# PROC091F_RST_GPIOs_I2C.net
KiCad netlist of a schematic drawn in Altium Designer
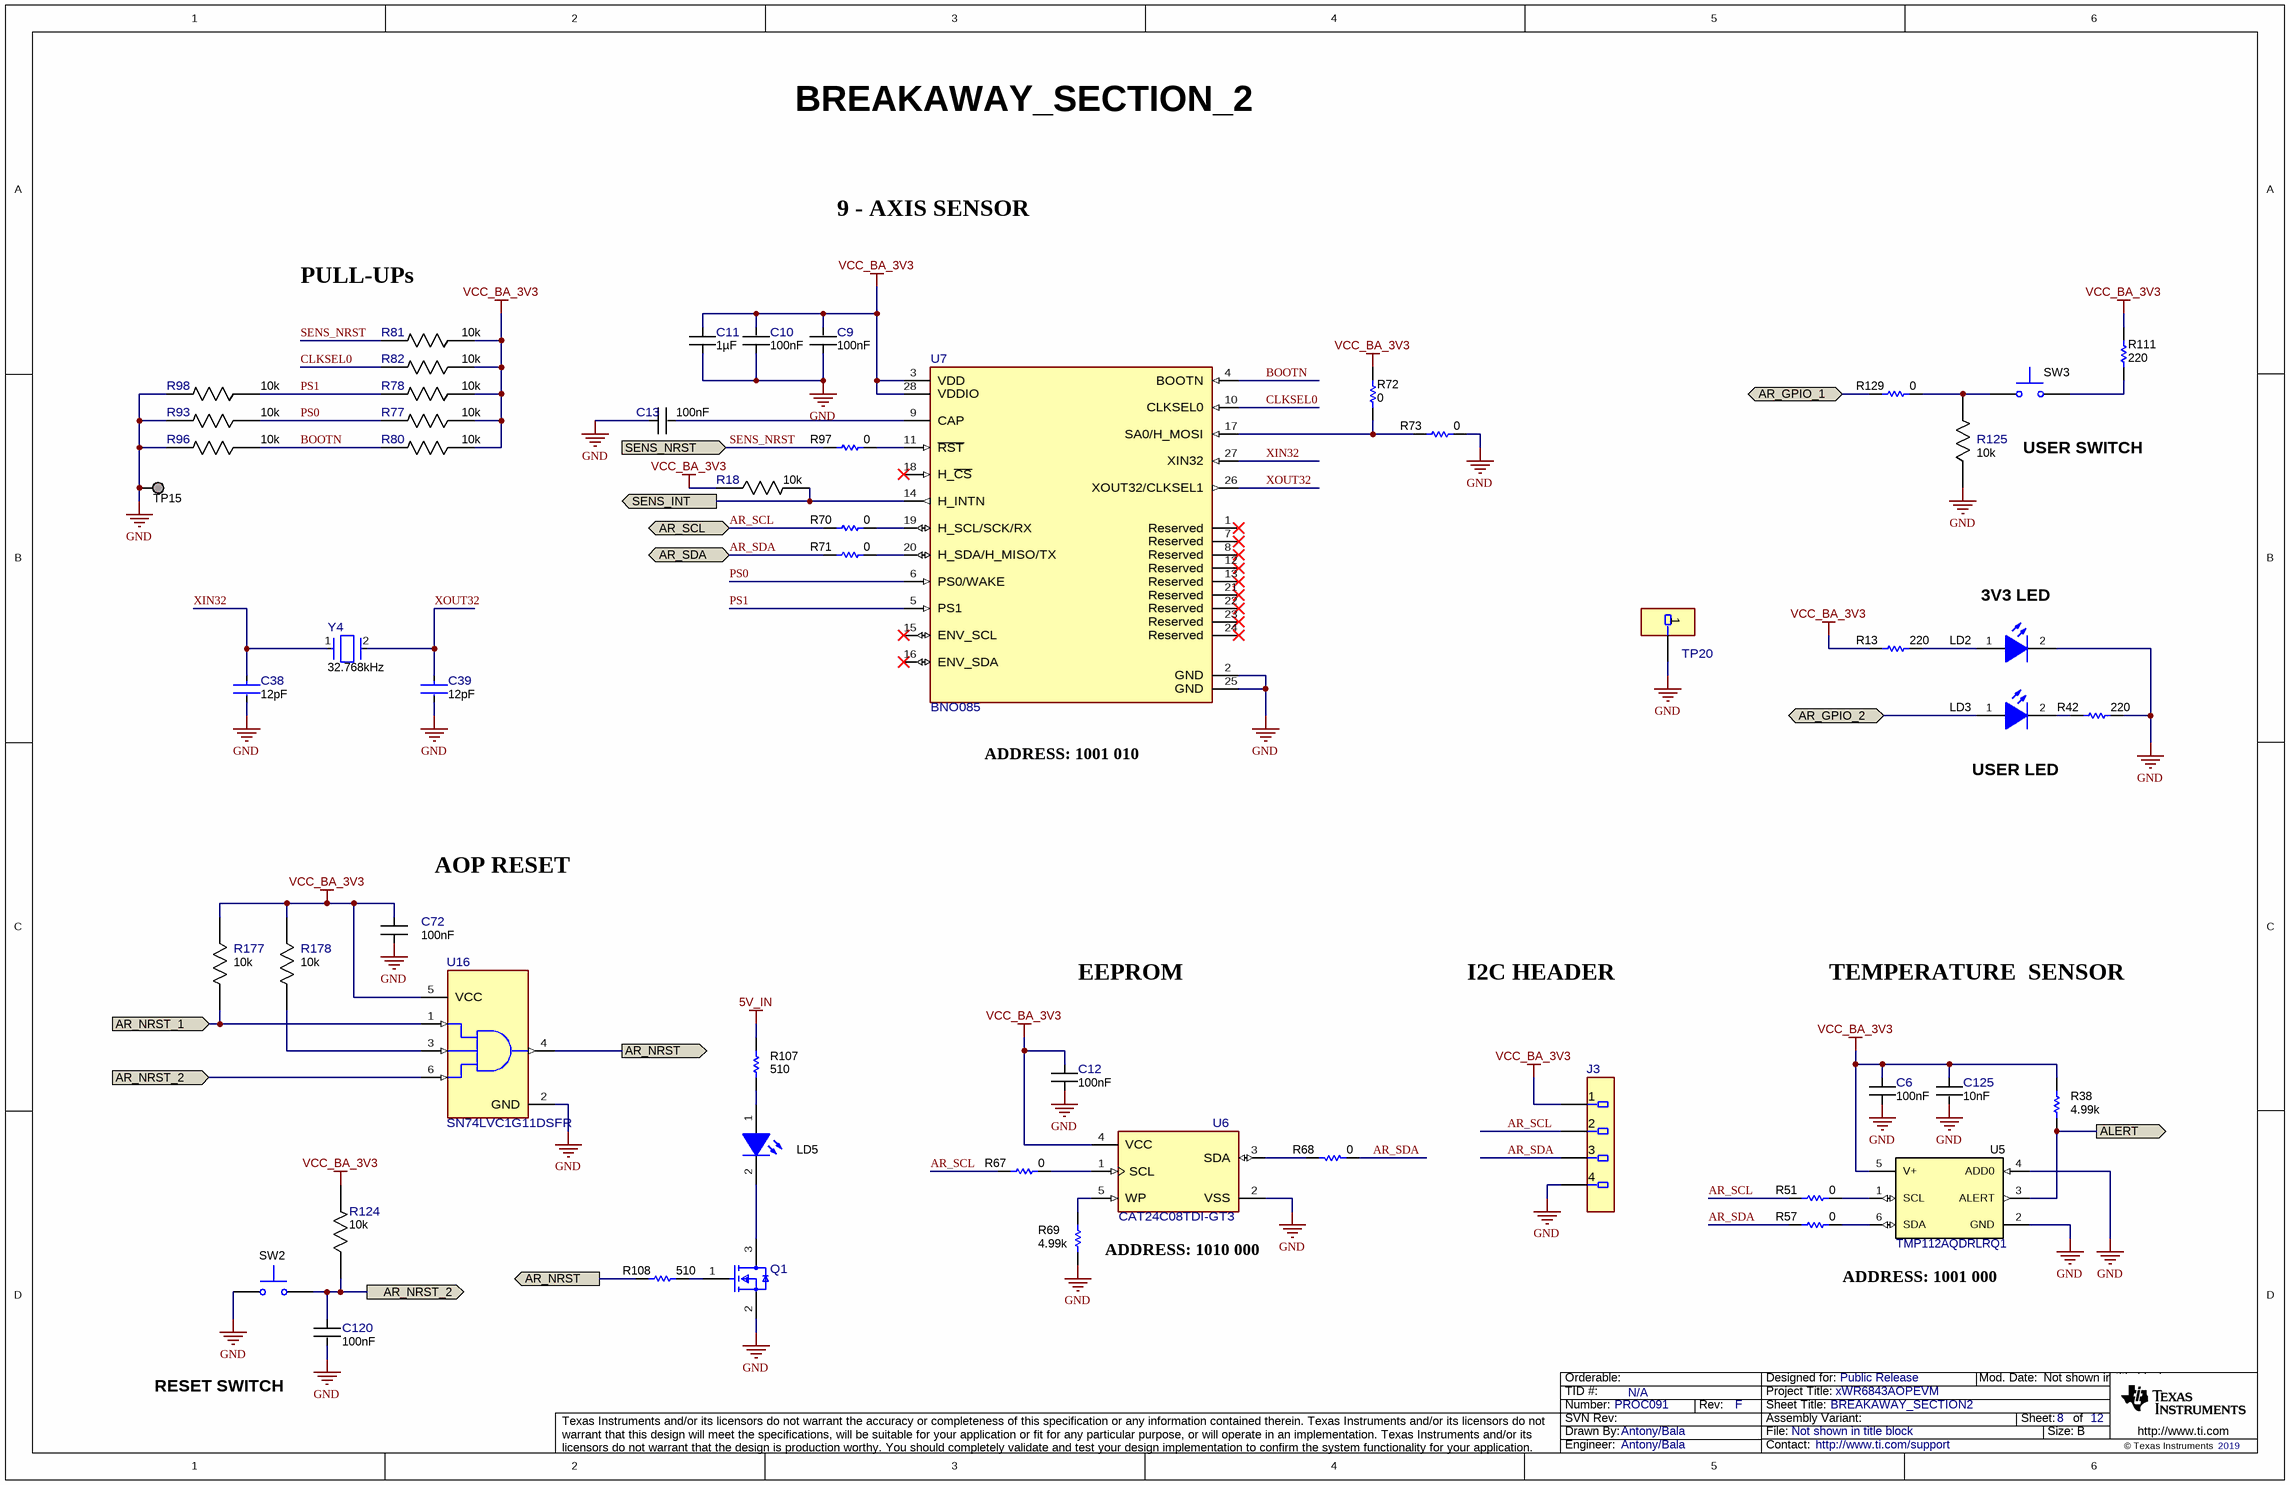
[diagram p0: PROC091F_RST_GPIOs_I2C.SchDoc]

(export (version "E")
  (design (tool "Eeschema 10.0.6"))
  (components
    (comp (ref "C6")
      (value "GRM033R6YA104KE14D")
      (footprint "FP-GRM033R6YA104KE14D_0201 (0603 Metric)-IPC_C")
      (description "Cap Ceramic 0.1uF 35V X5R 10% Pad SMD 0201 85C T/R")
      (fields (field (name "CAP_F") "100nF") (field (name "MANUFACTURER") "Murata Electronics North America"))
      (libsource (lib "Altium Vault - TI") (part "SYM-B32642B0223J"))
    )
    (comp (ref "C9")
      (value "GRM033R6YA104KE14D")
      (footprint "FP-GRM033R6YA104KE14D_0201 (0603 Metric)-IPC_C")
      (description "Cap Ceramic 0.1uF 35V X5R 10% Pad SMD 0201 85C T/R")
      (fields (field (name "CAP_F") "100nF") (field (name "MANUFACTURER") "Murata Electronics North America"))
      (libsource (lib "Altium Vault - TI") (part "SYM-B32642B0223J"))
    )
    (comp (ref "C10")
      (value "GRM033R6YA104KE14D")
      (footprint "FP-GRM033R6YA104KE14D_0201 (0603 Metric)-IPC_C")
      (description "Cap Ceramic 0.1uF 35V X5R 10% Pad SMD 0201 85C T/R")
      (fields (field (name "CAP_F") "100nF") (field (name "MANUFACTURER") "Murata Electronics North America"))
      (libsource (lib "Altium Vault - TI") (part "SYM-B32642B0223J"))
    )
    (comp (ref "C11")
      (value "CL03A105MO3NRNH")
      (footprint "FP-CL03A105MO3NRNH_0201-IPC_C")
      (description "1µF ±20% 16V Ceramic Capacitor X5R 0201")
      (fields (field (name "CAP_F") "1µF") (field (name "MANUFACTURER") "Samsung Electro-Mechanics"))
      (libsource (lib "Altium Vault - TI") (part "SYM-B32642B0223J"))
    )
    (comp (ref "C12")
      (value "GRM033R6YA104KE14D")
      (footprint "FP-GRM033R6YA104KE14D_0201 (0603 Metric)-IPC_C")
      (description "Cap Ceramic 0.1uF 35V X5R 10% Pad SMD 0201 85C T/R")
      (fields (field (name "CAP_F") "100nF") (field (name "MANUFACTURER") "Murata Electronics North America"))
      (libsource (lib "Altium Vault - TI") (part "SYM-B32642B0223J"))
    )
    (comp (ref "C13")
      (value "GRM033R6YA104KE14D")
      (footprint "FP-GRM033R6YA104KE14D_0201 (0603 Metric)-IPC_C")
      (description "Cap Ceramic 0.1uF 35V X5R 10% Pad SMD 0201 85C T/R")
      (fields (field (name "CAP_F") "100nF") (field (name "MANUFACTURER") "Murata Electronics North America"))
      (libsource (lib "Altium Vault - TI") (part "SYM-B32642B0223J"))
    )
    (comp (ref "C38")
      (value "250R05L120JV4T")
      (footprint "FP-250R05L120JV4T_0201-IPC_C")
      (description "CAP CER 12PF 25V C0G/NP0 0201")
      (fields (field (name "CAP_F") "12pF") (field (name "MANUFACTURER") "Johanson Technology Inc."))
      (libsource (lib "Altium Vault - TI") (part "SYM-CL31B335KAHVPNE"))
    )
    (comp (ref "C39")
      (value "250R05L120JV4T")
      (footprint "FP-250R05L120JV4T_0201-IPC_C")
      (description "CAP CER 12PF 25V C0G/NP0 0201")
      (fields (field (name "CAP_F") "12pF") (field (name "MANUFACTURER") "Johanson Technology Inc."))
      (libsource (lib "Altium Vault - TI") (part "SYM-CL31B335KAHVPNE"))
    )
    (comp (ref "C72")
      (value "GRM033R6YA104KE14D")
      (footprint "FP-GRM033R6YA104KE14D_0201 (0603 Metric)-IPC_C")
      (description "Cap Ceramic 0.1uF 35V X5R 10% Pad SMD 0201 85C T/R")
      (fields (field (name "CAP_F") "100nF") (field (name "MANUFACTURER") "Murata Electronics North America"))
      (libsource (lib "Altium Vault - TI") (part "SYM-B32642B0223J"))
    )
    (comp (ref "C120")
      (value "GRM033R6YA104KE14D")
      (footprint "FP-GRM033R6YA104KE14D_0201 (0603 Metric)-IPC_C")
      (description "Cap Ceramic 0.1uF 35V X5R 10% Pad SMD 0201 85C T/R")
      (fields (field (name "CAP_F") "100nF") (field (name "MANUFACTURER") "Murata Electronics North America"))
      (libsource (lib "Altium Vault - TI") (part "SYM-B32642B0223J"))
    )
    (comp (ref "C125")
      (value "CL03A103KA3NNNC")
      (footprint "FP-CL03A103KA3NNNC_0201-IPC_C")
      (description "CAP CER 10000PF 25V X5R 0201")
      (fields
        (field (name "CAP_F") "10nF")
        (field (name "MANUFACTURER") "Samsung Electro-Mechanics America, Inc")
      )
      (libsource (lib "Altium Vault - TI") (part "SYM-B32642B0223J"))
    )
    (comp (ref "J3")
      (value "M50-3930442")
      (footprint "FP-M50-3930442_HDR4-Recommended_Land_Pattern")
      (description "CONN HDR 1.27MM R/A AU 4POS")
      (fields (field (name "MANUFACTURER") "Harwin Inc."))
      (libsource (lib "Altium Vault - TI") (part "SYM-M50-3930442"))
    )
    (comp (ref "LD2")
      (value "APHHS1005CGCK")
      (footprint "APHHS1005_Green")
      (description "LED, Green, SMD")
      (fields (field (name "MANUFACTURER") "Kingbright"))
      (libsource (lib "Altium Vault - TI") (part "LED"))
    )
    (comp (ref "LD3")
      (value "APHHS1005CGCK")
      (footprint "APHHS1005_Green")
      (description "LED, Green, SMD")
      (fields (field (name "MANUFACTURER") "Kingbright"))
      (libsource (lib "Altium Vault - TI") (part "LED"))
    )
    (comp (ref "LD5")
      (value "APHHS1005CGCK")
      (footprint "APHHS1005_Green")
      (description "LED, Green, SMD")
      (fields (field (name "MANUFACTURER") "Kingbright"))
      (libsource (lib "Altium Vault - TI") (part "LED"))
    )
    (comp (ref "Q1")
      (value "BSS123-7-F")
      (footprint "FP-BSS123-7-F_SOT23-IPC_C")
      (description "MOSFET N-CH 100V 170MA SOT23-3")
      (fields (field (name "MANUFACTURER") "Diodes Incorporated"))
      (libsource (lib "Altium Vault - TI") (part "SYM-BSS123-7-F"))
    )
    (comp (ref "R13")
      (value "220")
      (footprint "0201L")
      (description "RES, 220, 5%, 0.05 W, 0201")
      (fields
        (field (name "MANUFACTURER") "Yageo America")
        (field (name "PARTNUMBER") "RC0201JR-07220RL")
        (field (name "PUBLISHER") "Texas Instruments")
      )
      (libsource (lib "Altium Vault - TI") (part "Resistor"))
    )
    (comp (ref "R18")
      (value "RR0306P-103-D")
      (footprint "FP-RR0306P-103-D_0201-IPC_C")
      (description "10 kOhms ±0.5% 0.05W, 1/20W Chip Resistor 0201 (0603 Metric)  Thin Film")
      (fields (field (name "MANUFACTURER") "Susumu") (field (name "RES_OHM") "10k"))
      (libsource (lib "Altium Vault - TI") (part "SYM-PMR18EZPJ000"))
    )
    (comp (ref "R38")
      (value "4.99k")
      (footprint "0201L")
      (description "RES, 4.99 k, 1%, 0.05 W, 0201")
      (fields
        (field (name "MANUFACTURER") "Yageo America")
        (field (name "PARTNUMBER") "RC0201FR-074K99L")
        (field (name "PUBLISHER") "Texas Instruments")
      )
      (libsource (lib "Altium Vault - TI") (part "Resistor"))
    )
    (comp (ref "R42")
      (value "220")
      (footprint "0201L")
      (description "RES, 220, 5%, 0.05 W, 0201")
      (fields
        (field (name "MANUFACTURER") "Yageo America")
        (field (name "PARTNUMBER") "RC0201JR-07220RL")
        (field (name "PUBLISHER") "Texas Instruments")
      )
      (libsource (lib "Altium Vault - TI") (part "Resistor"))
    )
    (comp (ref "R51")
      (value "RC0201JR-070RL")
      (footprint "FP-RC0201JR-070RL_0201 (0603 Metric)-MFG")
      (description "RES SMD 0 OHM JUMPER 1/20W 0201")
      (fields (field (name "MANUFACTURER") "Yageo") (field (name "RES_OHM") "0"))
      (libsource (lib "Altium Vault - TI") (part "SYM-WSR3R1500F"))
    )
    (comp (ref "R57")
      (value "RC0201JR-070RL")
      (footprint "FP-RC0201JR-070RL_0201 (0603 Metric)-MFG")
      (description "RES SMD 0 OHM JUMPER 1/20W 0201")
      (fields (field (name "MANUFACTURER") "Yageo") (field (name "RES_OHM") "0"))
      (libsource (lib "Altium Vault - TI") (part "SYM-WSR3R1500F"))
    )
    (comp (ref "R67")
      (value "RC0201JR-070RL")
      (footprint "FP-RC0201JR-070RL_0201 (0603 Metric)-MFG")
      (description "RES SMD 0 OHM JUMPER 1/20W 0201")
      (fields (field (name "MANUFACTURER") "Yageo") (field (name "RES_OHM") "0"))
      (libsource (lib "Altium Vault - TI") (part "SYM-WSR3R1500F"))
    )
    (comp (ref "R68")
      (value "RC0201JR-070RL")
      (footprint "FP-RC0201JR-070RL_0201 (0603 Metric)-MFG")
      (description "RES SMD 0 OHM JUMPER 1/20W 0201")
      (fields (field (name "MANUFACTURER") "Yageo") (field (name "RES_OHM") "0"))
      (libsource (lib "Altium Vault - TI") (part "SYM-WSR3R1500F"))
    )
    (comp (ref "R69")
      (value "4.99k")
      (footprint "0201L")
      (description "RES, 4.99 k, 1%, 0.05 W, 0201")
      (fields
        (field (name "MANUFACTURER") "Yageo America")
        (field (name "PARTNUMBER") "RC0201FR-074K99L")
        (field (name "PUBLISHER") "Texas Instruments")
      )
      (libsource (lib "Altium Vault - TI") (part "Resistor"))
    )
    (comp (ref "R70")
      (value "RC0201JR-070RL")
      (footprint "FP-RC0201JR-070RL_0201 (0603 Metric)-MFG")
      (description "RES SMD 0 OHM JUMPER 1/20W 0201")
      (fields (field (name "MANUFACTURER") "Yageo") (field (name "RES_OHM") "0"))
      (libsource (lib "Altium Vault - TI") (part "SYM-WSR3R1500F"))
    )
    (comp (ref "R71")
      (value "RC0201JR-070RL")
      (footprint "FP-RC0201JR-070RL_0201 (0603 Metric)-MFG")
      (description "RES SMD 0 OHM JUMPER 1/20W 0201")
      (fields (field (name "MANUFACTURER") "Yageo") (field (name "RES_OHM") "0"))
      (libsource (lib "Altium Vault - TI") (part "SYM-WSR3R1500F"))
    )
    (comp (ref "R72")
      (value "RC0201JR-070RL")
      (footprint "FP-RC0201JR-070RL_0201 (0603 Metric)-IPC_C")
      (description "RES SMD 0 OHM JUMPER 1/20W 0201")
      (fields (field (name "MANUFACTURER") "Yageo") (field (name "RES_OHM") "0"))
      (libsource (lib "Altium Vault - TI") (part "SYM-WSR3R1500F"))
    )
    (comp (ref "R73")
      (value "RC0201JR-070RL")
      (footprint "FP-RC0201JR-070RL_0201 (0603 Metric)-IPC_C")
      (description "RES SMD 0 OHM JUMPER 1/20W 0201")
      (fields (field (name "MANUFACTURER") "Yageo") (field (name "RES_OHM") "0"))
      (libsource (lib "Altium Vault - TI") (part "SYM-WSR3R1500F"))
    )
    (comp (ref "R77")
      (value "RR0306P-103-D")
      (footprint "FP-RR0306P-103-D_0201-IPC_C")
      (description "10 kOhms ±0.5% 0.05W, 1/20W Chip Resistor 0201 (0603 Metric)  Thin Film")
      (fields (field (name "MANUFACTURER") "Susumu") (field (name "RES_OHM") "10k"))
      (libsource (lib "Altium Vault - TI") (part "SYM-PMR18EZPJ000"))
    )
    (comp (ref "R78")
      (value "RR0306P-103-D")
      (footprint "FP-RR0306P-103-D_0201-IPC_C")
      (description "10 kOhms ±0.5% 0.05W, 1/20W Chip Resistor 0201 (0603 Metric)  Thin Film")
      (fields (field (name "MANUFACTURER") "Susumu") (field (name "RES_OHM") "10k"))
      (libsource (lib "Altium Vault - TI") (part "SYM-PMR18EZPJ000"))
    )
    (comp (ref "R80")
      (value "RR0306P-103-D")
      (footprint "FP-RR0306P-103-D_0201-IPC_C")
      (description "10 kOhms ±0.5% 0.05W, 1/20W Chip Resistor 0201 (0603 Metric)  Thin Film")
      (fields (field (name "MANUFACTURER") "Susumu") (field (name "RES_OHM") "10k"))
      (libsource (lib "Altium Vault - TI") (part "SYM-PMR18EZPJ000"))
    )
    (comp (ref "R81")
      (value "RR0306P-103-D")
      (footprint "FP-RR0306P-103-D_0201-IPC_C")
      (description "10 kOhms ±0.5% 0.05W, 1/20W Chip Resistor 0201 (0603 Metric)  Thin Film")
      (fields (field (name "MANUFACTURER") "Susumu") (field (name "RES_OHM") "10k"))
      (libsource (lib "Altium Vault - TI") (part "SYM-PMR18EZPJ000"))
    )
    (comp (ref "R82")
      (value "RR0306P-103-D")
      (footprint "FP-RR0306P-103-D_0201-IPC_C")
      (description "10 kOhms ±0.5% 0.05W, 1/20W Chip Resistor 0201 (0603 Metric)  Thin Film")
      (fields (field (name "MANUFACTURER") "Susumu") (field (name "RES_OHM") "10k"))
      (libsource (lib "Altium Vault - TI") (part "SYM-PMR18EZPJ000"))
    )
    (comp (ref "R93")
      (value "RR0306P-103-D")
      (footprint "FP-RR0306P-103-D_0201-IPC_C")
      (description "10 kOhms ±0.5% 0.05W, 1/20W Chip Resistor 0201 (0603 Metric)  Thin Film")
      (fields (field (name "MANUFACTURER") "Susumu") (field (name "RES_OHM") "10k"))
      (libsource (lib "Altium Vault - TI") (part "SYM-PMR18EZPJ000"))
    )
    (comp (ref "R96")
      (value "RR0306P-103-D")
      (footprint "FP-RR0306P-103-D_0201-IPC_C")
      (description "10 kOhms ±0.5% 0.05W, 1/20W Chip Resistor 0201 (0603 Metric)  Thin Film")
      (fields (field (name "MANUFACTURER") "Susumu") (field (name "RES_OHM") "10k"))
      (libsource (lib "Altium Vault - TI") (part "SYM-PMR18EZPJ000"))
    )
    (comp (ref "R97")
      (value "RC0201JR-070RL")
      (footprint "FP-RC0201JR-070RL_0201 (0603 Metric)-IPC_C")
      (description "RES SMD 0 OHM JUMPER 1/20W 0201")
      (fields (field (name "MANUFACTURER") "Yageo") (field (name "RES_OHM") "0"))
      (libsource (lib "Altium Vault - TI") (part "SYM-WSR3R1500F"))
    )
    (comp (ref "R98")
      (value "RR0306P-103-D")
      (footprint "FP-RR0306P-103-D_0201-IPC_C")
      (description "10 kOhms ±0.5% 0.05W, 1/20W Chip Resistor 0201 (0603 Metric)  Thin Film")
      (fields (field (name "MANUFACTURER") "Susumu") (field (name "RES_OHM") "10k"))
      (libsource (lib "Altium Vault - TI") (part "SYM-PMR18EZPJ000"))
    )
    (comp (ref "R107")
      (value "510")
      (footprint "0201L")
      (description "RES, 510, 5%, 0.05 W, 0201")
      (fields
        (field (name "MANUFACTURER") "Yageo America")
        (field (name "PARTNUMBER") "RC0201JR-07510RL")
        (field (name "PUBLISHER") "Texas Instruments")
      )
      (libsource (lib "Altium Vault - TI") (part "Resistor"))
    )
    (comp (ref "R108")
      (value "510")
      (footprint "0201L")
      (description "RES, 510, 5%, 0.05 W, 0201")
      (fields
        (field (name "MANUFACTURER") "Yageo America")
        (field (name "PARTNUMBER") "RC0201JR-07510RL")
        (field (name "PUBLISHER") "Texas Instruments")
      )
      (libsource (lib "Altium Vault - TI") (part "Resistor"))
    )
    (comp (ref "R111")
      (value "220")
      (footprint "0201L")
      (description "RES, 220, 5%, 0.05 W, 0201")
      (fields
        (field (name "MANUFACTURER") "Yageo America")
        (field (name "PARTNUMBER") "RC0201JR-07220RL")
        (field (name "PUBLISHER") "Texas Instruments")
      )
      (libsource (lib "Altium Vault - TI") (part "Resistor"))
    )
    (comp (ref "R124")
      (value "RR0306P-103-D")
      (footprint "FP-RR0306P-103-D_0201-IPC_C")
      (description "10 kOhms ±0.5% 0.05W, 1/20W Chip Resistor 0201 (0603 Metric)  Thin Film")
      (fields (field (name "MANUFACTURER") "Susumu") (field (name "RES_OHM") "10k"))
      (libsource (lib "Altium Vault - TI") (part "SYM-PMR18EZPJ000"))
    )
    (comp (ref "R125")
      (value "RR0306P-103-D")
      (footprint "FP-RR0306P-103-D_0201-IPC_C")
      (description "10 kOhms ±0.5% 0.05W, 1/20W Chip Resistor 0201 (0603 Metric)  Thin Film")
      (fields (field (name "MANUFACTURER") "Susumu") (field (name "RES_OHM") "10k"))
      (libsource (lib "Altium Vault - TI") (part "SYM-PMR18EZPJ000"))
    )
    (comp (ref "R129")
      (value "RC0201JR-070RL")
      (footprint "FP-RC0201JR-070RL_0201 (0603 Metric)-IPC_C")
      (description "RES SMD 0 OHM JUMPER 1/20W 0201")
      (fields (field (name "MANUFACTURER") "Yageo") (field (name "RES_OHM") "0"))
      (libsource (lib "Altium Vault - TI") (part "SYM-WSR3R1500F"))
    )
    (comp (ref "R177")
      (value "RR0306P-103-D")
      (footprint "FP-RR0306P-103-D_0201-IPC_C")
      (description "10 kOhms ±0.5% 0.05W, 1/20W Chip Resistor 0201 (0603 Metric)  Thin Film")
      (fields (field (name "MANUFACTURER") "Susumu") (field (name "RES_OHM") "10k"))
      (libsource (lib "Altium Vault - TI") (part "SYM-PMR18EZPJ000"))
    )
    (comp (ref "R178")
      (value "RR0306P-103-D")
      (footprint "FP-RR0306P-103-D_0201-IPC_C")
      (description "10 kOhms ±0.5% 0.05W, 1/20W Chip Resistor 0201 (0603 Metric)  Thin Film")
      (fields (field (name "MANUFACTURER") "Susumu") (field (name "RES_OHM") "10k"))
      (libsource (lib "Altium Vault - TI") (part "SYM-PMR18EZPJ000"))
    )
    (comp (ref "SW2")
      (value "B3U-1000P")
      (footprint "SW_B3U-1000P")
      (description "SWITCH TACTILE SPST-NO 0.05A 12V")
      (fields
        (field (name "MANUFACTURER") "Omron Electronic Components")
        (field (name "PUBLISHER") "Texas Instruments")
      )
      (libsource (lib "Altium Vault - TI") (part "Switch_PushButton"))
    )
    (comp (ref "SW3")
      (value "B3U-1000P")
      (footprint "SW_B3U-1000P")
      (description "SWITCH TACTILE SPST-NO 0.05A 12V")
      (fields
        (field (name "MANUFACTURER") "Omron Electronic Components")
        (field (name "PUBLISHER") "Texas Instruments")
      )
      (libsource (lib "Altium Vault - TI") (part "Switch_PushButton"))
    )
    (comp (ref "TP15")
      (value "TESTPOINT")
      (footprint "TP_25MIL-SMT")
      (description "TEST POINT.  No entry in BOM.")
      (libsource (lib "Altium Vault - TI") (part "TESTPOINT"))
    )
    (comp (ref "TP20")
      (value "4953")
      (footprint "FP-4953_HDR1-MFG")
      (description "PC Test Point, Loop Brass, Tin Plating 0.047\" (1.19mm) Hole Diameter Mounting Type")
      (fields (field (name "MANUFACTURER") "Keystone Electronics"))
      (libsource (lib "Altium Vault - TI") (part "SYM-4953"))
    )
    (comp (ref "U5")
      (value "TMP112AQDRLRQ1")
      (footprint "DRL0006A")
      (fields
        (field (name "MANUFACTURER") "Texas Instruments")
        (field (name "PUBLISHER") "Texas Instruments")
      )
      (libsource (lib "Altium Vault - TI") (part "TMP112"))
    )
    (comp (ref "U6")
      (value "CAT24C08TDI-GT3")
      (footprint "FP-CAT24C08TDI-GT3_TSOT-23-5-IPC_A")
      (description "8KB I2C SER EEPROM TSOT 23")
      (fields (field (name "MANUFACTURER") "ON Semiconductor"))
      (libsource (lib "Altium Vault - TI") (part "SYM-CAT24C08TDI-GT3"))
    )
    (comp (ref "U7")
      (value "BNO085")
      (footprint "FP-BNO085_LGA28-MFG")
      (description "IMU ACCEL/GYRO/MAG I2C 32BIT")
      (fields (field (name "MANUFACTURER") "Hillcrest Laboratories, Inc."))
      (libsource (lib "Altium Vault - TI") (part "SYM-BNO085"))
    )
    (comp (ref "U16")
      (value "SN74LVC1G11DSFR")
      (footprint "DSF0006A-MFG")
      (description "AND Gate IC 1 Channel  6-SON (1x1)")
      (fields
        (field (name "MOUSER PART NUMBER") "595-SN74LVC1G11DSFR")
        (field (name "DIGIKEY PART NUMBER") "296-30121-1-ND")
      )
      (libsource (lib "Altium Vault - TI") (part "SYM-SN74LVC1G11DSFR"))
    )
    (comp (ref "Y4")
      (value "ABS05W-32.768KHZ-D-2-T")
      (footprint "FP-ABS05W-32.768KHZ-D-2-T_XTAL_SMT_1MM6_1MM0-MFG")
      (description "CRYSTAL 32.768KHZ 4PF SMD")
      (fields (field (name "FREQUENCY_FIXED") "32.768kHz") (field (name "MANUFACTURER") "Abracon LLC"))
      (libsource (lib "Altium Vault - TI") (part "SYM-ABS05W-32.768KHZ-D-2-T"))
    )
  )
  (nets
    (net (code "1") (name "/ALERT") (class "Default")
      (node (ref "R38") (pin "1") (pinfunction "1_1") (pintype "passive"))
      (node (ref "U5") (pin "3") (pinfunction "ALERT_3") (pintype "output"))
    )
    (net (code "2") (name "/AR_GPIO_1") (class "Default")
      (node (ref "R129") (pin "2") (pinfunction "2_2") (pintype "passive"))
    )
    (net (code "3") (name "/AR_GPIO_2") (class "Default")
      (node (ref "LD3") (pin "1") (pinfunction "A_1") (pintype "passive"))
    )
    (net (code "4") (name "/AR_NRST") (class "Default")
      (node (ref "R108") (pin "1") (pinfunction "1_1") (pintype "passive"))
      (node (ref "U16") (pin "4") (pinfunction "Y_4") (pintype "output"))
    )
    (net (code "5") (name "/AR_NRST_1") (class "Default")
      (node (ref "R177") (pin "2") (pinfunction "2_2") (pintype "passive"))
      (node (ref "U16") (pin "1") (pinfunction "A_1") (pintype "input"))
    )
    (net (code "6") (name "/AR_NRST_2") (class "Default")
      (node (ref "C120") (pin "1") (pinfunction "1_1") (pintype "passive"))
      (node (ref "R124") (pin "1") (pinfunction "1_1") (pintype "passive"))
      (node (ref "SW2") (pin "1") (pinfunction "1_1") (pintype "passive"))
      (node (ref "U16") (pin "6") (pinfunction "C_6") (pintype "input"))
    )
    (net (code "7") (name "/AR_SCL") (class "Default")
      (node (ref "J3") (pin "2") (pinfunction "2_2") (pintype "passive"))
      (node (ref "R51") (pin "1") (pinfunction "1_1") (pintype "passive"))
      (node (ref "R67") (pin "1") (pinfunction "1_1") (pintype "passive"))
      (node (ref "R70") (pin "2") (pinfunction "2_2") (pintype "passive"))
    )
    (net (code "8") (name "/AR_SDA") (class "Default")
      (node (ref "J3") (pin "3") (pinfunction "3_3") (pintype "passive"))
      (node (ref "R57") (pin "1") (pinfunction "1_1") (pintype "passive"))
      (node (ref "R68") (pin "1") (pinfunction "1_1") (pintype "passive"))
      (node (ref "R71") (pin "2") (pinfunction "2_2") (pintype "passive"))
    )
    (net (code "9") (name "/BOOTN") (class "Default")
      (node (ref "R80") (pin "2") (pinfunction "2_2") (pintype "passive"))
      (node (ref "R96") (pin "1") (pinfunction "1_1") (pintype "passive"))
      (node (ref "U7") (pin "4") (pinfunction "BOOTN_4") (pintype "input"))
    )
    (net (code "10") (name "/CLKSEL0") (class "Default")
      (node (ref "R82") (pin "2") (pinfunction "2_2") (pintype "passive"))
      (node (ref "U7") (pin "10") (pinfunction "CLKSEL0_10") (pintype "input"))
    )
    (net (code "11") (name "/PS0") (class "Default")
      (node (ref "R77") (pin "2") (pinfunction "2_2") (pintype "passive"))
      (node (ref "R93") (pin "1") (pinfunction "1_1") (pintype "passive"))
      (node (ref "U7") (pin "6") (pinfunction "PS0/WAKE_6") (pintype "input"))
    )
    (net (code "12") (name "/PS1") (class "Default")
      (node (ref "R78") (pin "2") (pinfunction "2_2") (pintype "passive"))
      (node (ref "R98") (pin "1") (pinfunction "1_1") (pintype "passive"))
      (node (ref "U7") (pin "5") (pinfunction "PS1_5") (pintype "input"))
    )
    (net (code "13") (name "/SENS_INT") (class "Default")
      (node (ref "R18") (pin "2") (pinfunction "2_2") (pintype "passive"))
      (node (ref "U7") (pin "14") (pinfunction "H_INTN_14") (pintype "output"))
    )
    (net (code "14") (name "/SENS_NRST") (class "Default")
      (node (ref "R81") (pin "2") (pinfunction "2_2") (pintype "passive"))
      (node (ref "R97") (pin "2") (pinfunction "2_2") (pintype "passive"))
    )
    (net (code "15") (name "/XIN32") (class "Default")
      (node (ref "C38") (pin "1") (pinfunction "1_1") (pintype "passive"))
      (node (ref "U7") (pin "27") (pinfunction "XIN32_27") (pintype "input"))
      (node (ref "Y4") (pin "1") (pinfunction "1_1") (pintype "passive"))
    )
    (net (code "16") (name "/XOUT32") (class "Default")
      (node (ref "C39") (pin "1") (pinfunction "1_1") (pintype "passive"))
      (node (ref "U7") (pin "26") (pinfunction "XOUT32/CLKSEL1_26") (pintype "output"))
      (node (ref "Y4") (pin "2") (pinfunction "2_2") (pintype "passive"))
    )
    (net (code "17") (name "5V_IN") (class "Default")
      (node (ref "R107") (pin "1") (pinfunction "1_1") (pintype "passive"))
    )
    (net (code "18") (name "GND") (class "Default")
      (node (ref "C10") (pin "1") (pinfunction "1_1") (pintype "passive"))
      (node (ref "C11") (pin "2") (pinfunction "2_2") (pintype "passive"))
      (node (ref "C12") (pin "1") (pinfunction "1_1") (pintype "passive"))
      (node (ref "C120") (pin "2") (pinfunction "2_2") (pintype "passive"))
      (node (ref "C125") (pin "2") (pinfunction "2_2") (pintype "passive"))
      (node (ref "C13") (pin "1") (pinfunction "1_1") (pintype "passive"))
      (node (ref "C38") (pin "2") (pinfunction "2_2") (pintype "passive"))
      (node (ref "C39") (pin "2") (pinfunction "2_2") (pintype "passive"))
      (node (ref "C6") (pin "1") (pinfunction "1_1") (pintype "passive"))
      (node (ref "C72") (pin "1") (pinfunction "1_1") (pintype "passive"))
      (node (ref "C9") (pin "1") (pinfunction "1_1") (pintype "passive"))
      (node (ref "J3") (pin "4") (pinfunction "4_4") (pintype "passive"))
      (node (ref "LD2") (pin "2") (pinfunction "K_2") (pintype "passive"))
      (node (ref "Q1") (pin "2") (pinfunction "S_2") (pintype "passive"))
      (node (ref "R125") (pin "1") (pinfunction "1_1") (pintype "passive"))
      (node (ref "R42") (pin "2") (pinfunction "2_2") (pintype "passive"))
      (node (ref "R69") (pin "1") (pinfunction "1_1") (pintype "passive"))
      (node (ref "R73") (pin "1") (pinfunction "1_1") (pintype "passive"))
      (node (ref "R93") (pin "2") (pinfunction "2_2") (pintype "passive"))
      (node (ref "R96") (pin "2") (pinfunction "2_2") (pintype "passive"))
      (node (ref "R98") (pin "2") (pinfunction "2_2") (pintype "passive"))
      (node (ref "SW2") (pin "2") (pinfunction "2_2") (pintype "passive"))
      (node (ref "TP15") (pin "1") (pintype "passive"))
      (node (ref "TP20") (pin "1") (pinfunction "1_1") (pintype "passive"))
      (node (ref "U16") (pin "2") (pinfunction "GND_2") (pintype "power_in"))
      (node (ref "U5") (pin "2") (pinfunction "GND_2") (pintype "power_in"))
      (node (ref "U5") (pin "4") (pinfunction "ADD0_4") (pintype "input"))
      (node (ref "U6") (pin "2") (pinfunction "VSS_2") (pintype "power_in"))
      (node (ref "U7") (pin "2") (pinfunction "GND_2") (pintype "power_in"))
      (node (ref "U7") (pin "25") (pinfunction "GND_25") (pintype "power_in"))
    )
    (net (code "19") (name "Net-(LD2-A)") (class "Default")
      (node (ref "LD2") (pin "1") (pinfunction "A_1") (pintype "passive"))
      (node (ref "R13") (pin "2") (pinfunction "2_2") (pintype "passive"))
    )
    (net (code "20") (name "Net-(LD3-K)") (class "Default")
      (node (ref "LD3") (pin "2") (pinfunction "K_2") (pintype "passive"))
      (node (ref "R42") (pin "1") (pinfunction "1_1") (pintype "passive"))
    )
    (net (code "21") (name "Net-(LD5-A)") (class "Default")
      (node (ref "LD5") (pin "1") (pinfunction "A_1") (pintype "passive"))
      (node (ref "R107") (pin "2") (pinfunction "2_2") (pintype "passive"))
    )
    (net (code "22") (name "Net-(LD5-K)") (class "Default")
      (node (ref "LD5") (pin "2") (pinfunction "K_2") (pintype "passive"))
      (node (ref "Q1") (pin "3") (pinfunction "D_3") (pintype "passive"))
    )
    (net (code "23") (name "Net-(Q1-G)") (class "Default")
      (node (ref "Q1") (pin "1") (pinfunction "G_1") (pintype "passive"))
      (node (ref "R108") (pin "2") (pinfunction "2_2") (pintype "passive"))
    )
    (net (code "24") (name "Net-(R111-Pad1)") (class "Default")
      (node (ref "R111") (pin "1") (pinfunction "1_1") (pintype "passive"))
      (node (ref "SW3") (pin "2") (pinfunction "2_2") (pintype "passive"))
    )
    (net (code "25") (name "Net-(R125-Pad2)") (class "Default")
      (node (ref "R125") (pin "2") (pinfunction "2_2") (pintype "passive"))
      (node (ref "R129") (pin "1") (pinfunction "1_1") (pintype "passive"))
      (node (ref "SW3") (pin "1") (pinfunction "1_1") (pintype "passive"))
    )
    (net (code "26") (name "Net-(U5-SCL)") (class "Default")
      (node (ref "R51") (pin "2") (pinfunction "2_2") (pintype "passive"))
      (node (ref "U5") (pin "1") (pinfunction "SCL_1") (pintype "bidirectional"))
    )
    (net (code "27") (name "Net-(U5-SDA)") (class "Default")
      (node (ref "R57") (pin "2") (pinfunction "2_2") (pintype "passive"))
      (node (ref "U5") (pin "6") (pinfunction "SDA_6") (pintype "bidirectional"))
    )
    (net (code "28") (name "Net-(U6-SCL)") (class "Default")
      (node (ref "R67") (pin "2") (pinfunction "2_2") (pintype "passive"))
      (node (ref "U6") (pin "1") (pinfunction "SCL_1") (pintype "input"))
    )
    (net (code "29") (name "Net-(U6-SDA)") (class "Default")
      (node (ref "R68") (pin "2") (pinfunction "2_2") (pintype "passive"))
      (node (ref "U6") (pin "3") (pinfunction "SDA_3") (pintype "bidirectional"))
    )
    (net (code "30") (name "Net-(U6-WP)") (class "Default")
      (node (ref "R69") (pin "2") (pinfunction "2_2") (pintype "passive"))
      (node (ref "U6") (pin "5") (pinfunction "WP_5") (pintype "input"))
    )
    (net (code "31") (name "Net-(U7-CAP)") (class "Default")
      (node (ref "C13") (pin "2") (pinfunction "2_2") (pintype "passive"))
      (node (ref "U7") (pin "9") (pinfunction "CAP_9") (pintype "passive"))
    )
    (net (code "32") (name "Net-(U7-H_SCL{slash}SCK{slash}RX)") (class "Default")
      (node (ref "R70") (pin "1") (pinfunction "1_1") (pintype "passive"))
      (node (ref "U7") (pin "19") (pinfunction "H_SCL/SCK/RX_19") (pintype "bidirectional"))
    )
    (net (code "33") (name "Net-(U7-H_SDA{slash}H_MISO{slash}TX)") (class "Default")
      (node (ref "R71") (pin "1") (pinfunction "1_1") (pintype "passive"))
      (node (ref "U7") (pin "20") (pinfunction "H_SDA/H_MISO/TX_20") (pintype "bidirectional"))
    )
    (net (code "34") (name "Net-(U7-SA0{slash}H_MOSI)") (class "Default")
      (node (ref "R72") (pin "2") (pinfunction "2_2") (pintype "passive"))
      (node (ref "R73") (pin "2") (pinfunction "2_2") (pintype "passive"))
      (node (ref "U7") (pin "17") (pinfunction "SA0/H_MOSI_17") (pintype "input"))
    )
    (net (code "35") (name "Net-(U7-~{RST})") (class "Default")
      (node (ref "R97") (pin "1") (pinfunction "1_1") (pintype "passive"))
      (node (ref "U7") (pin "11") (pinfunction "~{RST}_11") (pintype "input"))
    )
    (net (code "36") (name "Net-(U16-B)") (class "Default")
      (node (ref "R178") (pin "2") (pinfunction "2_2") (pintype "passive"))
      (node (ref "U16") (pin "3") (pinfunction "B_3") (pintype "input"))
    )
    (net (code "37") (name "VCC_BA_3V3") (class "Default")
      (node (ref "C10") (pin "2") (pinfunction "2_2") (pintype "passive"))
      (node (ref "C11") (pin "1") (pinfunction "1_1") (pintype "passive"))
      (node (ref "C12") (pin "2") (pinfunction "2_2") (pintype "passive"))
      (node (ref "C125") (pin "1") (pinfunction "1_1") (pintype "passive"))
      (node (ref "C6") (pin "2") (pinfunction "2_2") (pintype "passive"))
      (node (ref "C72") (pin "2") (pinfunction "2_2") (pintype "passive"))
      (node (ref "C9") (pin "2") (pinfunction "2_2") (pintype "passive"))
      (node (ref "J3") (pin "1") (pinfunction "1_1") (pintype "passive"))
      (node (ref "R111") (pin "2") (pinfunction "2_2") (pintype "passive"))
      (node (ref "R124") (pin "2") (pinfunction "2_2") (pintype "passive"))
      (node (ref "R13") (pin "1") (pinfunction "1_1") (pintype "passive"))
      (node (ref "R177") (pin "1") (pinfunction "1_1") (pintype "passive"))
      (node (ref "R178") (pin "1") (pinfunction "1_1") (pintype "passive"))
      (node (ref "R18") (pin "1") (pinfunction "1_1") (pintype "passive"))
      (node (ref "R38") (pin "2") (pinfunction "2_2") (pintype "passive"))
      (node (ref "R72") (pin "1") (pinfunction "1_1") (pintype "passive"))
      (node (ref "R77") (pin "1") (pinfunction "1_1") (pintype "passive"))
      (node (ref "R78") (pin "1") (pinfunction "1_1") (pintype "passive"))
      (node (ref "R80") (pin "1") (pinfunction "1_1") (pintype "passive"))
      (node (ref "R81") (pin "1") (pinfunction "1_1") (pintype "passive"))
      (node (ref "R82") (pin "1") (pinfunction "1_1") (pintype "passive"))
      (node (ref "U16") (pin "5") (pinfunction "VCC_5") (pintype "power_in"))
      (node (ref "U5") (pin "5") (pinfunction "V+_5") (pintype "power_in"))
      (node (ref "U6") (pin "4") (pinfunction "VCC_4") (pintype "power_in"))
      (node (ref "U7") (pin "28") (pinfunction "VDDIO_28") (pintype "power_in"))
      (node (ref "U7") (pin "3") (pinfunction "VDD_3") (pintype "power_in"))
    )
    (net (code "38") (name "unconnected-(U7-ENV_SCL-Pad15)") (class "Default")
      (node (ref "U7") (pin "15") (pinfunction "ENV_SCL_15") (pintype "bidirectional+no_connect"))
    )
    (net (code "39") (name "unconnected-(U7-ENV_SDA-Pad16)") (class "Default")
      (node (ref "U7") (pin "16") (pinfunction "ENV_SDA_16") (pintype "bidirectional+no_connect"))
    )
    (net (code "40") (name "unconnected-(U7-H_~{CS}-Pad18)") (class "Default")
      (node (ref "U7") (pin "18") (pinfunction "H_~{CS}_18") (pintype "input+no_connect"))
    )
    (net (code "41") (name "unconnected-(U7-Reserved-Pad1)") (class "Default")
      (node (ref "U7") (pin "1") (pinfunction "Reserved_1") (pintype "passive+no_connect"))
    )
    (net (code "42") (name "unconnected-(U7-Reserved-Pad7)") (class "Default")
      (node (ref "U7") (pin "7") (pinfunction "Reserved_7") (pintype "passive+no_connect"))
    )
    (net (code "43") (name "unconnected-(U7-Reserved-Pad8)") (class "Default")
      (node (ref "U7") (pin "8") (pinfunction "Reserved_8") (pintype "passive+no_connect"))
    )
    (net (code "44") (name "unconnected-(U7-Reserved-Pad12)") (class "Default")
      (node (ref "U7") (pin "12") (pinfunction "Reserved_12") (pintype "passive+no_connect"))
    )
    (net (code "45") (name "unconnected-(U7-Reserved-Pad13)") (class "Default")
      (node (ref "U7") (pin "13") (pinfunction "Reserved_13") (pintype "passive+no_connect"))
    )
    (net (code "46") (name "unconnected-(U7-Reserved-Pad21)") (class "Default")
      (node (ref "U7") (pin "21") (pinfunction "Reserved_21") (pintype "passive+no_connect"))
    )
    (net (code "47") (name "unconnected-(U7-Reserved-Pad22)") (class "Default")
      (node (ref "U7") (pin "22") (pinfunction "Reserved_22") (pintype "passive+no_connect"))
    )
    (net (code "48") (name "unconnected-(U7-Reserved-Pad23)") (class "Default")
      (node (ref "U7") (pin "23") (pinfunction "Reserved_23") (pintype "passive+no_connect"))
    )
    (net (code "49") (name "unconnected-(U7-Reserved-Pad24)") (class "Default")
      (node (ref "U7") (pin "24") (pinfunction "Reserved_24") (pintype "passive+no_connect"))
    )
  )
)
